# 5V_Power_Supply.net
KiCad netlist of a schematic drawn in EAGLE
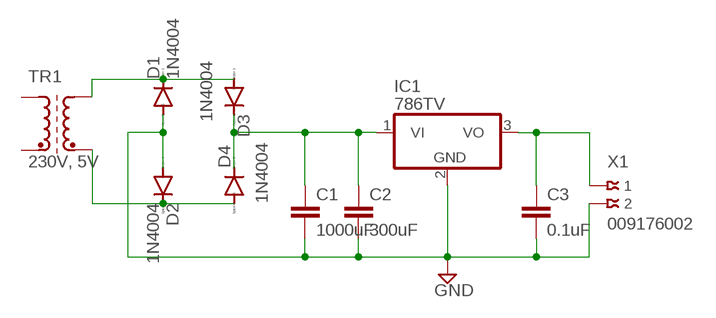
[diagram p0: schematic, sheet 1]

(export (version "E")
  (design (tool "Eeschema 10.0.6"))
  (components
    (comp (ref "C1")
      (value "1000uF")
      (footprint "eagle-import:C2.5-2")
      (libsource (lib "eagle-import") (part "C2.5/2"))
    )
    (comp (ref "C2")
      (value "300uF")
      (footprint "eagle-import:C2.5-2")
      (libsource (lib "eagle-import") (part "C2.5/2"))
    )
    (comp (ref "C3")
      (value "0.1uF")
      (footprint "eagle-import:C2.5-2")
      (libsource (lib "eagle-import") (part "C2.5/2"))
    )
    (comp (ref "D1")
      (value "1N4004")
      (footprint "eagle-import:DO41-10")
      (libsource (lib "eagle-import") (part "1N4004"))
    )
    (comp (ref "D2")
      (value "1N4004")
      (footprint "eagle-import:DO41-10")
      (libsource (lib "eagle-import") (part "1N4004"))
    )
    (comp (ref "D3")
      (value "1N4004")
      (footprint "eagle-import:DO41-10")
      (libsource (lib "eagle-import") (part "1N4004"))
    )
    (comp (ref "D4")
      (value "1N4004")
      (footprint "eagle-import:DO41-10")
      (libsource (lib "eagle-import") (part "1N4004"))
    )
    (comp (ref "IC1")
      (value "786TV")
      (footprint "eagle-import:TO220V")
      (libsource (lib "eagle-import") (part "78TV6"))
    )
    (comp (ref "TR1")
      (value "230V, 5V")
      (footprint "eagle-import:SM-T4")
      (libsource (lib "eagle-import") (part "SM-T4"))
    )
    (comp (ref "X1")
      (value "009176002")
      (footprint "eagle-import:009176002")
      (fields (field (name "MPN") "009176002001006"))
      (libsource (lib "eagle-import") (part "00917?0026"))
    )
  )
  (nets
    (net (code "1") (name "GND") (class "Default")
      (node (ref "C1") (pin "2") (pinfunction "2_2") (pintype "passive"))
      (node (ref "C2") (pin "2") (pinfunction "2_2") (pintype "passive"))
      (node (ref "C3") (pin "2") (pinfunction "2_2") (pintype "passive"))
      (node (ref "D1") (pin "A") (pinfunction "A_A") (pintype "passive"))
      (node (ref "D2") (pin "A") (pinfunction "A_A") (pintype "passive"))
      (node (ref "IC1") (pin "2") (pinfunction "GND_2") (pintype "passive"))
      (node (ref "X1") (pin "2") (pinfunction "2_2") (pintype "passive"))
    )
    (net (code "2") (name "Net-(IC1-VI)") (class "Default")
      (node (ref "C1") (pin "1") (pinfunction "1_1") (pintype "passive"))
      (node (ref "C2") (pin "1") (pinfunction "1_1") (pintype "passive"))
      (node (ref "D3") (pin "C") (pinfunction "C_C") (pintype "passive"))
      (node (ref "D4") (pin "C") (pinfunction "C_C") (pintype "passive"))
      (node (ref "IC1") (pin "1") (pinfunction "VI_1") (pintype "input"))
    )
    (net (code "3") (name "Net-(IC1-VO)") (class "Default")
      (node (ref "C3") (pin "1") (pinfunction "1_1") (pintype "passive"))
      (node (ref "IC1") (pin "3") (pinfunction "VO_3") (pintype "passive"))
      (node (ref "X1") (pin "1") (pinfunction "1_1") (pintype "passive"))
    )
    (net (code "4") (name "Net-(TR1-A2)") (class "Default")
      (node (ref "D1") (pin "C") (pinfunction "C_C") (pintype "passive"))
      (node (ref "D3") (pin "A") (pinfunction "A_A") (pintype "passive"))
      (node (ref "TR1") (pin "5") (pinfunction "A2_5") (pintype "passive"))
    )
    (net (code "5") (name "Net-(TR1-E2)") (class "Default")
      (node (ref "D2") (pin "C") (pinfunction "C_C") (pintype "passive"))
      (node (ref "D4") (pin "A") (pinfunction "A_A") (pintype "passive"))
      (node (ref "TR1") (pin "4") (pinfunction "E2_4") (pintype "passive"))
    )
    (net (code "6") (name "unconnected-(TR1-A1-Pad1)") (class "Default")
      (node (ref "TR1") (pin "1") (pinfunction "A1_1") (pintype "passive"))
    )
    (net (code "7") (name "unconnected-(TR1-E1-Pad2)") (class "Default")
      (node (ref "TR1") (pin "2") (pinfunction "E1_2") (pintype "passive"))
    )
  )
)
